# PiTopConn.net
KiCad netlist of a schematic drawn in Altium Designer
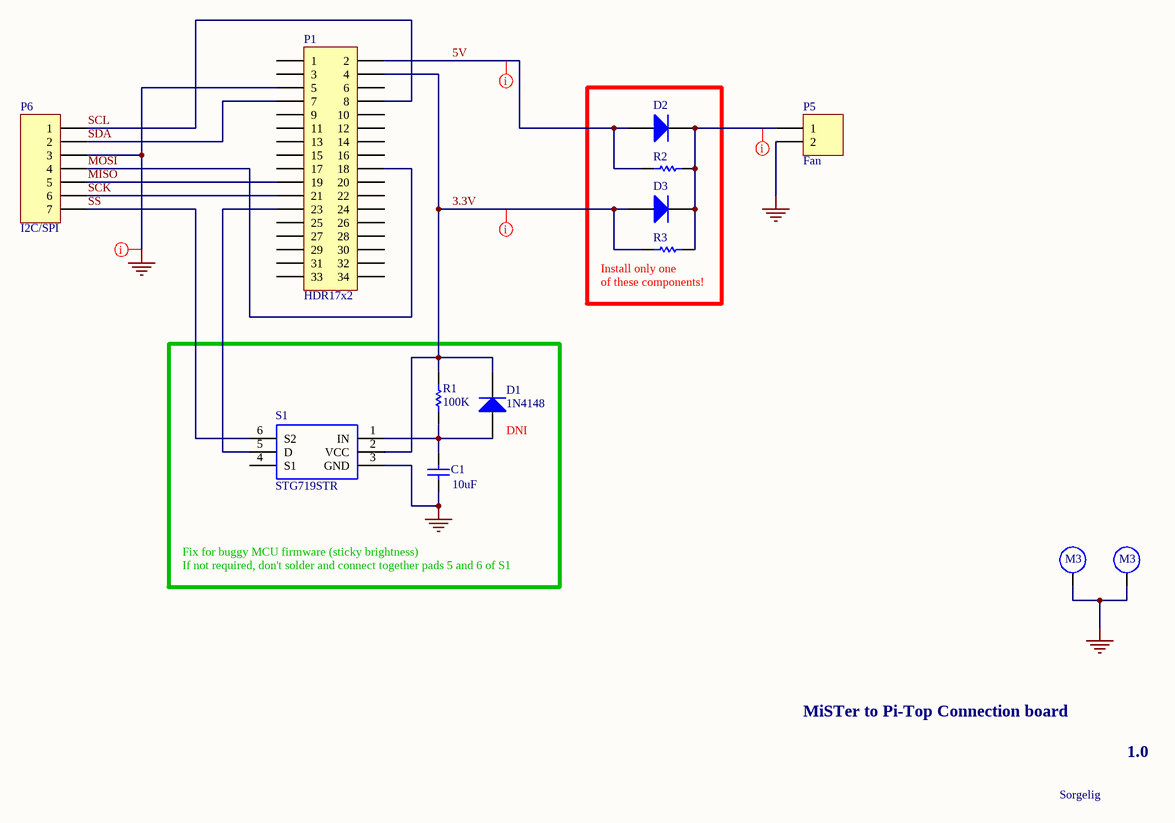
[diagram p0: PiTopConn.SchDoc]

(export (version "E")
  (design (tool "Eeschema 10.0.6"))
  (components
    (comp (ref "C1")
      (value "10uF")
      (footprint "C0805")
      (description "Ceramic Chip Capacitor - Standard")
      (fields (field (name "Comment") "C0805") (field (name "PUBLISHER") "Altium Limited"))
      (libsource (lib "KEMET Chip Capacitor") (part "C0805"))
    )
    (comp (ref "D1")
      (value "1N4148")
      (footprint "DIODE")
      (description "Default Diode")
      (fields (field (name "PUBLISHER") "Altium Limited"))
      (libsource (lib "Miscellaneous Devices") (part "Diode"))
    )
    (comp (ref "D2")
      (value "Diode")
      (description "Default Diode")
      (fields (field (name "PUBLISHER") "Altium Limited"))
      (libsource (lib "Miscellaneous Devices") (part "Diode"))
    )
    (comp (ref "D3")
      (value "Diode")
      (description "Default Diode")
      (fields (field (name "PUBLISHER") "Altium Limited"))
      (libsource (lib "Miscellaneous Devices") (part "Diode"))
    )
    (comp (ref "H1") (value "M3") (footprint "M3") (libsource (lib "lib") (part "M3")))
    (comp (ref "H2") (value "M3") (footprint "M3") (libsource (lib "lib") (part "M3")))
    (comp (ref "P1") (value "HDR17x2") (footprint "HDR17X2_90") (libsource (lib "lib") (part "HDR17x2")))
    (comp (ref "P5")
      (value "Fan")
      (footprint "HDR1X2")
      (description "Header, 2-Pin")
      (fields (field (name "PUBLISHER") "Altium Limited"))
      (libsource (lib "Miscellaneous Connectors") (part "Header 2"))
    )
    (comp (ref "P6")
      (value "I2C/SPI")
      (footprint "HDR1X7")
      (description "Header, 7-Pin")
      (fields (field (name "PUBLISHER") "Altium Limited"))
      (libsource (lib "Miscellaneous Connectors") (part "Header 7"))
    )
    (comp (ref "R1")
      (value "100K")
      (footprint "R0805")
      (fields (field (name "PUBLISHER") "Altium Limited"))
      (libsource (lib "Panasonic Resistor") (part "ERJ6RS"))
    )
    (comp (ref "R2")
      (value "10")
      (footprint "6-0805")
      (fields (field (name "PUBLISHER") "Altium Limited"))
      (libsource (lib "Panasonic Resistor") (part "ERJ6RS"))
    )
    (comp (ref "R3")
      (value "10")
      (footprint "6-0805")
      (fields (field (name "PUBLISHER") "Altium Limited"))
      (libsource (lib "Panasonic Resistor") (part "ERJ6RS"))
    )
    (comp (ref "S1")
      (value "STG719STR")
      (footprint "SOT23-6_L")
      (description "STMICROELECTRONICS - STG719STR - IC, SWITCH, SPDT, SMD")
      (libsource (lib "lib") (part "STG719STR"))
    )
  )
  (nets
    (net (code "1") (name "/3.3V") (class "Default")
      (node (ref "D1") (pin "2") (pinfunction "K_2") (pintype "passive"))
      (node (ref "D3") (pin "1") (pinfunction "A_1") (pintype "passive"))
      (node (ref "P1") (pin "4") (pinfunction "4_4") (pintype "passive"))
      (node (ref "R1") (pin "2") (pinfunction "2_2") (pintype "passive"))
      (node (ref "R3") (pin "1") (pinfunction "1_1") (pintype "passive"))
      (node (ref "S1") (pin "2") (pinfunction "VCC_2") (pintype "passive"))
    )
    (net (code "2") (name "/5V") (class "Default")
      (node (ref "D2") (pin "1") (pinfunction "A_1") (pintype "passive"))
      (node (ref "P1") (pin "2") (pinfunction "2_2") (pintype "passive"))
      (node (ref "R2") (pin "1") (pinfunction "1_1") (pintype "passive"))
    )
    (net (code "3") (name "/MISO") (class "Default")
      (node (ref "P1") (pin "19") (pinfunction "19_19") (pintype "passive"))
      (node (ref "P6") (pin "5") (pinfunction "5_5") (pintype "passive"))
    )
    (net (code "4") (name "/MOSI") (class "Default")
      (node (ref "P1") (pin "18") (pinfunction "18_18") (pintype "passive"))
      (node (ref "P6") (pin "4") (pinfunction "4_4") (pintype "passive"))
    )
    (net (code "5") (name "/SCK") (class "Default")
      (node (ref "P1") (pin "21") (pinfunction "21_21") (pintype "passive"))
      (node (ref "P6") (pin "6") (pinfunction "6_6") (pintype "passive"))
    )
    (net (code "6") (name "/SCL") (class "Default")
      (node (ref "P1") (pin "8") (pinfunction "8_8") (pintype "passive"))
      (node (ref "P6") (pin "1") (pinfunction "1_1") (pintype "passive"))
    )
    (net (code "7") (name "/SDA") (class "Default")
      (node (ref "P1") (pin "7") (pinfunction "7_7") (pintype "passive"))
      (node (ref "P6") (pin "2") (pinfunction "2_2") (pintype "passive"))
    )
    (net (code "8") (name "/SS") (class "Default")
      (node (ref "P6") (pin "7") (pinfunction "7_7") (pintype "passive"))
      (node (ref "S1") (pin "6") (pinfunction "S2_6") (pintype "passive"))
    )
    (net (code "9") (name "GND") (class "Default")
      (node (ref "C1") (pin "1") (pinfunction "1_1") (pintype "passive"))
      (node (ref "H1") (pin "1") (pinfunction "1_1") (pintype "passive"))
      (node (ref "H2") (pin "1") (pinfunction "1_1") (pintype "passive"))
      (node (ref "P1") (pin "5") (pinfunction "5_5") (pintype "passive"))
      (node (ref "P5") (pin "2") (pinfunction "2_2") (pintype "passive"))
      (node (ref "P6") (pin "3") (pinfunction "3_3") (pintype "passive"))
      (node (ref "S1") (pin "3") (pinfunction "GND_3") (pintype "passive"))
    )
    (net (code "10") (name "Net-(D1-A)") (class "Default")
      (node (ref "C1") (pin "2") (pinfunction "2_2") (pintype "passive"))
      (node (ref "D1") (pin "1") (pinfunction "A_1") (pintype "passive"))
      (node (ref "R1") (pin "1") (pinfunction "1_1") (pintype "passive"))
      (node (ref "S1") (pin "1") (pinfunction "IN_1") (pintype "passive"))
    )
    (net (code "11") (name "Net-(D2-K)") (class "Default")
      (node (ref "D2") (pin "2") (pinfunction "K_2") (pintype "passive"))
      (node (ref "D3") (pin "2") (pinfunction "K_2") (pintype "passive"))
      (node (ref "P5") (pin "1") (pinfunction "1_1") (pintype "passive"))
      (node (ref "R2") (pin "2") (pinfunction "2_2") (pintype "passive"))
      (node (ref "R3") (pin "2") (pinfunction "2_2") (pintype "passive"))
    )
    (net (code "12") (name "Net-(S1-D)") (class "Default")
      (node (ref "P1") (pin "23") (pinfunction "23_23") (pintype "passive"))
      (node (ref "S1") (pin "5") (pinfunction "D_5") (pintype "passive"))
    )
    (net (code "13") (name "unconnected-(P1-Pad1)") (class "Default")
      (node (ref "P1") (pin "1") (pinfunction "1_1") (pintype "passive"))
    )
    (net (code "14") (name "unconnected-(P1-Pad3)") (class "Default")
      (node (ref "P1") (pin "3") (pinfunction "3_3") (pintype "passive"))
    )
    (net (code "15") (name "unconnected-(P1-Pad6)") (class "Default")
      (node (ref "P1") (pin "6") (pinfunction "6_6") (pintype "passive"))
    )
    (net (code "16") (name "unconnected-(P1-Pad9)") (class "Default")
      (node (ref "P1") (pin "9") (pinfunction "9_9") (pintype "passive"))
    )
    (net (code "17") (name "unconnected-(P1-Pad10)") (class "Default")
      (node (ref "P1") (pin "10") (pinfunction "10_10") (pintype "passive"))
    )
    (net (code "18") (name "unconnected-(P1-Pad11)") (class "Default")
      (node (ref "P1") (pin "11") (pinfunction "11_11") (pintype "passive"))
    )
    (net (code "19") (name "unconnected-(P1-Pad12)") (class "Default")
      (node (ref "P1") (pin "12") (pinfunction "12_12") (pintype "passive"))
    )
    (net (code "20") (name "unconnected-(P1-Pad13)") (class "Default")
      (node (ref "P1") (pin "13") (pinfunction "13_13") (pintype "passive"))
    )
    (net (code "21") (name "unconnected-(P1-Pad14)") (class "Default")
      (node (ref "P1") (pin "14") (pinfunction "14_14") (pintype "passive"))
    )
    (net (code "22") (name "unconnected-(P1-Pad15)") (class "Default")
      (node (ref "P1") (pin "15") (pinfunction "15_15") (pintype "passive"))
    )
    (net (code "23") (name "unconnected-(P1-Pad16)") (class "Default")
      (node (ref "P1") (pin "16") (pinfunction "16_16") (pintype "passive"))
    )
    (net (code "24") (name "unconnected-(P1-Pad17)") (class "Default")
      (node (ref "P1") (pin "17") (pinfunction "17_17") (pintype "passive"))
    )
    (net (code "25") (name "unconnected-(P1-Pad20)") (class "Default")
      (node (ref "P1") (pin "20") (pinfunction "20_20") (pintype "passive"))
    )
    (net (code "26") (name "unconnected-(P1-Pad22)") (class "Default")
      (node (ref "P1") (pin "22") (pinfunction "22_22") (pintype "passive"))
    )
    (net (code "27") (name "unconnected-(P1-Pad24)") (class "Default")
      (node (ref "P1") (pin "24") (pinfunction "24_24") (pintype "passive"))
    )
    (net (code "28") (name "unconnected-(P1-Pad25)") (class "Default")
      (node (ref "P1") (pin "25") (pinfunction "25_25") (pintype "passive"))
    )
    (net (code "29") (name "unconnected-(P1-Pad26)") (class "Default")
      (node (ref "P1") (pin "26") (pinfunction "26_26") (pintype "passive"))
    )
    (net (code "30") (name "unconnected-(P1-Pad27)") (class "Default")
      (node (ref "P1") (pin "27") (pinfunction "27_27") (pintype "passive"))
    )
    (net (code "31") (name "unconnected-(P1-Pad28)") (class "Default")
      (node (ref "P1") (pin "28") (pinfunction "28_28") (pintype "passive"))
    )
    (net (code "32") (name "unconnected-(P1-Pad29)") (class "Default")
      (node (ref "P1") (pin "29") (pinfunction "29_29") (pintype "passive"))
    )
    (net (code "33") (name "unconnected-(P1-Pad30)") (class "Default")
      (node (ref "P1") (pin "30") (pinfunction "30_30") (pintype "passive"))
    )
    (net (code "34") (name "unconnected-(P1-Pad31)") (class "Default")
      (node (ref "P1") (pin "31") (pinfunction "31_31") (pintype "passive"))
    )
    (net (code "35") (name "unconnected-(P1-Pad32)") (class "Default")
      (node (ref "P1") (pin "32") (pinfunction "32_32") (pintype "passive"))
    )
    (net (code "36") (name "unconnected-(P1-Pad33)") (class "Default")
      (node (ref "P1") (pin "33") (pinfunction "33_33") (pintype "passive"))
    )
    (net (code "37") (name "unconnected-(P1-Pad34)") (class "Default")
      (node (ref "P1") (pin "34") (pinfunction "34_34") (pintype "passive"))
    )
    (net (code "38") (name "unconnected-(S1-S1-Pad4)") (class "Default")
      (node (ref "S1") (pin "4") (pinfunction "S1_4") (pintype "passive"))
    )
  )
)
